# Barebones_ATMega328P.net
KiCad netlist of a schematic drawn in EAGLE
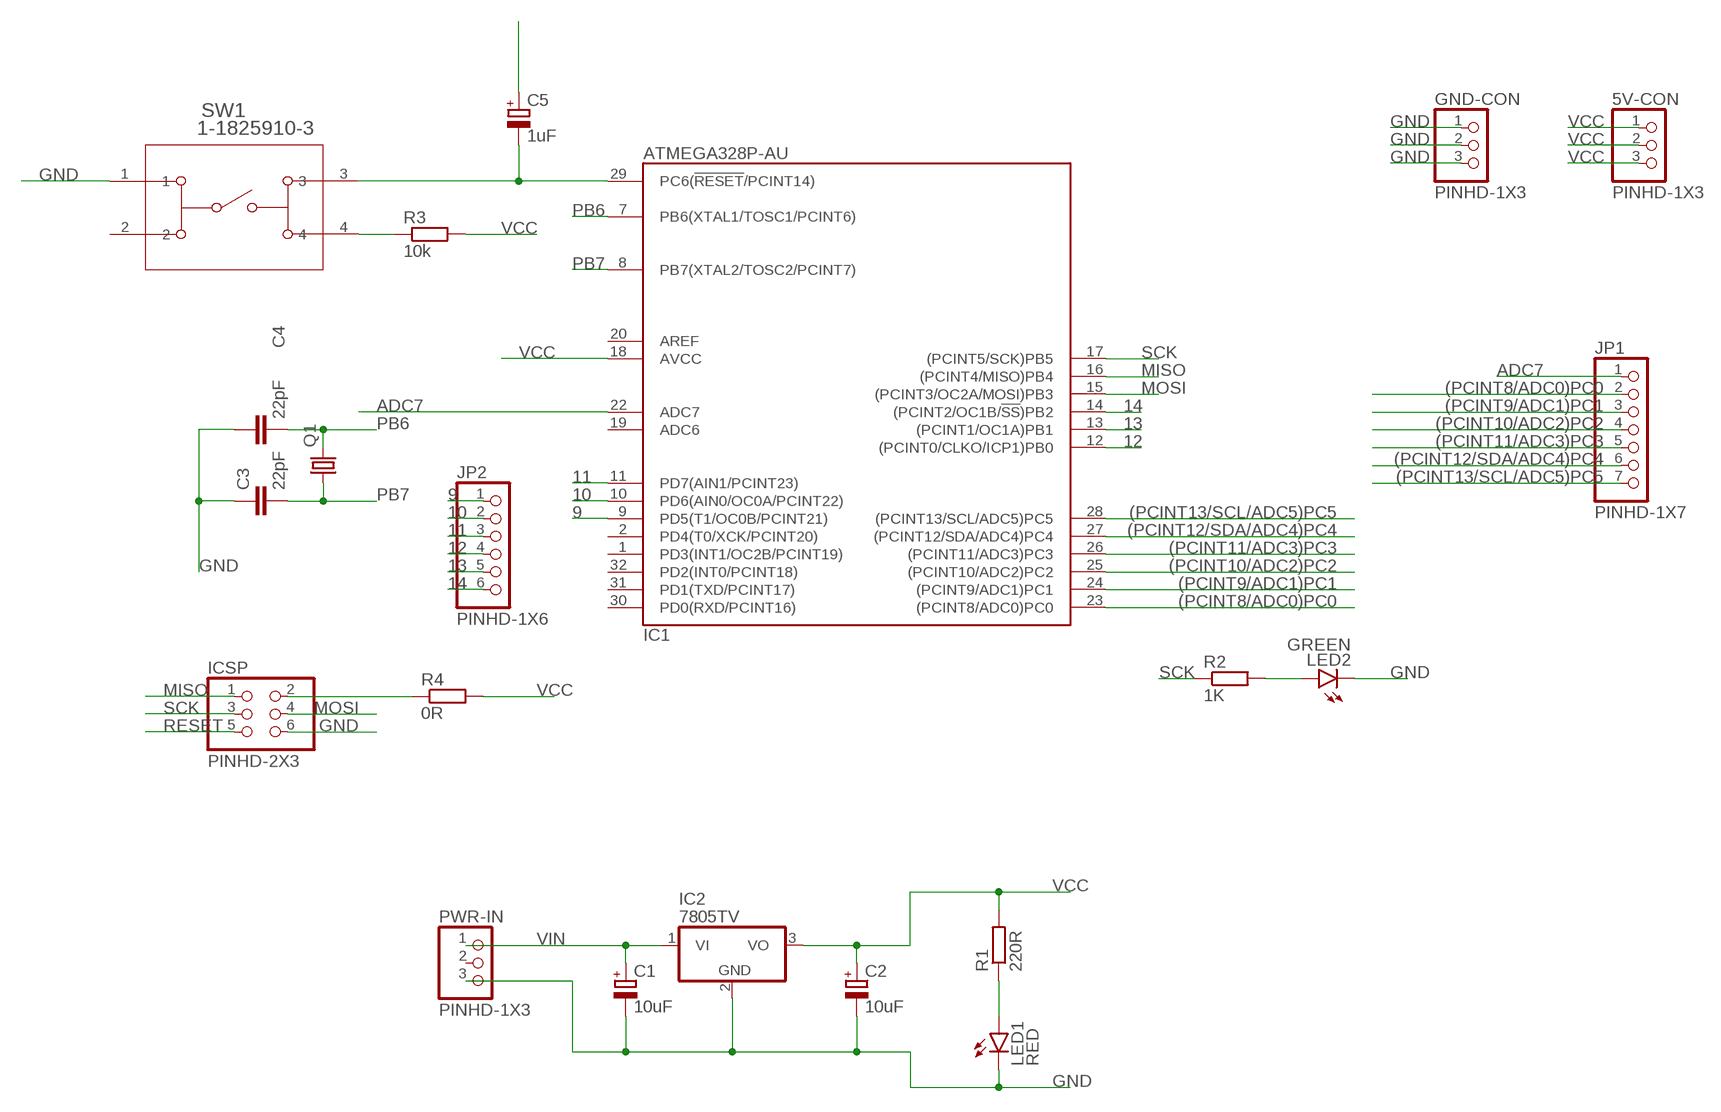
[diagram p0: schematic, sheet 1]

(export (version "E")
  (design (tool "Eeschema 10.0.6"))
  (components
    (comp (ref "5V-CON")
      (value "PINHD-1X3")
      (footprint "eagle-import:1X03")
      (libsource (lib "eagle-import") (part "PINHD-1X3"))
    )
    (comp (ref "C1")
      (value "10uF")
      (footprint "eagle-import:E5-8,5")
      (libsource (lib "eagle-import") (part "CPOL-EUE5-8.5"))
    )
    (comp (ref "C2")
      (value "10uF")
      (footprint "eagle-import:E5-8,5")
      (libsource (lib "eagle-import") (part "CPOL-EUE5-8.5"))
    )
    (comp (ref "C3")
      (value "22pF")
      (footprint "eagle-import:C025-025X050")
      (libsource (lib "eagle-import") (part "C-EU025-025X050"))
    )
    (comp (ref "C4")
      (value "22pF")
      (footprint "eagle-import:C025-025X050")
      (libsource (lib "eagle-import") (part "C-EU025-025X050"))
    )
    (comp (ref "C5")
      (value "1uF")
      (footprint "eagle-import:E5-8,5")
      (libsource (lib "eagle-import") (part "CPOL-EUE5-8.5"))
    )
    (comp (ref "GND-CON")
      (value "PINHD-1X3")
      (footprint "eagle-import:1X03")
      (libsource (lib "eagle-import") (part "PINHD-1X3"))
    )
    (comp (ref "IC1")
      (value "ATMEGA328P-AU")
      (footprint "eagle-import:QFP32_7X7_0.80")
      (libsource (lib "eagle-import") (part "ATMEGA8P-AU32"))
    )
    (comp (ref "IC2")
      (value "7805TV")
      (footprint "eagle-import:TO220V")
      (libsource (lib "eagle-import") (part "78TV05"))
    )
    (comp (ref "ICSP")
      (value "PINHD-2X3")
      (footprint "eagle-import:2X03")
      (libsource (lib "eagle-import") (part "PINHD-2X3"))
    )
    (comp (ref "JP1")
      (value "PINHD-1X7")
      (footprint "eagle-import:1X07")
      (libsource (lib "eagle-import") (part "PINHD-1X7"))
    )
    (comp (ref "JP2")
      (value "PINHD-1X6")
      (footprint "eagle-import:1X06")
      (libsource (lib "eagle-import") (part "PINHD-1X6"))
    )
    (comp (ref "LED1")
      (value "RED")
      (footprint "eagle-import:LED3MM")
      (libsource (lib "eagle-import") (part "LED3MM"))
    )
    (comp (ref "LED2")
      (value "GREEN")
      (footprint "eagle-import:LED3MM")
      (libsource (lib "eagle-import") (part "LED3MM"))
    )
    (comp (ref "PWR-IN")
      (value "PINHD-1X3")
      (footprint "eagle-import:1X03")
      (libsource (lib "eagle-import") (part "PINHD-1X3"))
    )
    (comp (ref "Q1")
      (value "CRYSTALHC49S")
      (footprint "eagle-import:HC49_S")
      (libsource (lib "eagle-import") (part "CRYSTALHC49S"))
    )
    (comp (ref "R1")
      (value "220R")
      (footprint "eagle-import:0207_10")
      (libsource (lib "eagle-import") (part "R-EU_0207/10"))
    )
    (comp (ref "R2")
      (value "1K")
      (footprint "eagle-import:0207_10")
      (libsource (lib "eagle-import") (part "R-EU_0207/10"))
    )
    (comp (ref "R3")
      (value "10k")
      (footprint "eagle-import:0207_10")
      (libsource (lib "eagle-import") (part "R-EU_0207/10"))
    )
    (comp (ref "R4")
      (value "0R")
      (footprint "eagle-import:0207_10")
      (libsource (lib "eagle-import") (part "R-EU_0207/10"))
    )
    (comp (ref "SW1")
      (value "1-1825910-3")
      (footprint "eagle-import:SW4_1825910-D")
      (fields (field (name "COPYRIGHT") "Copyright (C) 2016 Accelerated Designs. All rights reserved"))
      (libsource (lib "eagle-import") (part "1-1825910-3"))
    )
  )
  (nets
    (net (code "1") (name "/(PCINT8{slash}ADC0)PC0") (class "Default")
      (node (ref "IC1") (pin "23") (pinfunction "(PCINT8/ADC0)PC0_23") (pintype "bidirectional"))
      (node (ref "JP1") (pin "2") (pinfunction "2_2") (pintype "passive"))
    )
    (net (code "2") (name "/(PCINT9{slash}ADC1)PC1") (class "Default")
      (node (ref "IC1") (pin "24") (pinfunction "(PCINT9/ADC1)PC1_24") (pintype "bidirectional"))
      (node (ref "JP1") (pin "3") (pinfunction "3_3") (pintype "passive"))
    )
    (net (code "3") (name "/(PCINT10{slash}ADC2)PC2") (class "Default")
      (node (ref "IC1") (pin "25") (pinfunction "(PCINT10/ADC2)PC2_25") (pintype "bidirectional"))
      (node (ref "JP1") (pin "4") (pinfunction "4_4") (pintype "passive"))
    )
    (net (code "4") (name "/(PCINT11{slash}ADC3)PC3") (class "Default")
      (node (ref "IC1") (pin "26") (pinfunction "(PCINT11/ADC3)PC3_26") (pintype "bidirectional"))
      (node (ref "JP1") (pin "5") (pinfunction "5_5") (pintype "passive"))
    )
    (net (code "5") (name "/(PCINT12{slash}SDA{slash}ADC4)PC4") (class "Default")
      (node (ref "IC1") (pin "27") (pinfunction "(PCINT12/SDA/ADC4)PC4_27") (pintype "bidirectional"))
      (node (ref "JP1") (pin "6") (pinfunction "6_6") (pintype "passive"))
    )
    (net (code "6") (name "/(PCINT13{slash}SCL{slash}ADC5)PC5") (class "Default")
      (node (ref "IC1") (pin "28") (pinfunction "(PCINT13/SCL/ADC5)PC5_28") (pintype "bidirectional"))
      (node (ref "JP1") (pin "7") (pinfunction "7_7") (pintype "passive"))
    )
    (net (code "7") (name "/9") (class "Default")
      (node (ref "IC1") (pin "9") (pinfunction "PD5(T1/OC0B/PCINT21)_9") (pintype "bidirectional"))
      (node (ref "JP2") (pin "1") (pinfunction "1_1") (pintype "passive"))
    )
    (net (code "8") (name "/10") (class "Default")
      (node (ref "IC1") (pin "10") (pinfunction "PD6(AIN0/OC0A/PCINT22)_10") (pintype "bidirectional"))
      (node (ref "JP2") (pin "2") (pinfunction "2_2") (pintype "passive"))
    )
    (net (code "9") (name "/11") (class "Default")
      (node (ref "IC1") (pin "11") (pinfunction "PD7(AIN1/PCINT23)_11") (pintype "bidirectional"))
      (node (ref "JP2") (pin "3") (pinfunction "3_3") (pintype "passive"))
    )
    (net (code "10") (name "/12") (class "Default")
      (node (ref "IC1") (pin "12") (pinfunction "(PCINT0/CLKO/ICP1)PB0_12") (pintype "bidirectional"))
      (node (ref "JP2") (pin "4") (pinfunction "4_4") (pintype "passive"))
    )
    (net (code "11") (name "/13") (class "Default")
      (node (ref "IC1") (pin "13") (pinfunction "(PCINT1/OC1A)PB1_13") (pintype "bidirectional"))
      (node (ref "JP2") (pin "5") (pinfunction "5_5") (pintype "passive"))
    )
    (net (code "12") (name "/14") (class "Default")
      (node (ref "IC1") (pin "14") (pinfunction "(PCINT2/OC1B/~{SS})PB2_14") (pintype "bidirectional"))
      (node (ref "JP2") (pin "6") (pinfunction "6_6") (pintype "passive"))
    )
    (net (code "13") (name "/ADC7") (class "Default")
      (node (ref "IC1") (pin "22") (pinfunction "ADC7_22") (pintype "bidirectional"))
      (node (ref "JP1") (pin "1") (pinfunction "1_1") (pintype "passive"))
    )
    (net (code "14") (name "/GND") (class "Default")
      (node (ref "C1") (pin "-") (pinfunction "-_-") (pintype "passive"))
      (node (ref "C2") (pin "-") (pinfunction "-_-") (pintype "passive"))
      (node (ref "C3") (pin "1") (pinfunction "1_1") (pintype "passive"))
      (node (ref "C4") (pin "1") (pinfunction "1_1") (pintype "passive"))
      (node (ref "GND-CON") (pin "1") (pinfunction "1_1") (pintype "passive"))
      (node (ref "GND-CON") (pin "2") (pinfunction "2_2") (pintype "passive"))
      (node (ref "GND-CON") (pin "3") (pinfunction "3_3") (pintype "passive"))
      (node (ref "IC2") (pin "2") (pinfunction "GND_2") (pintype "passive"))
      (node (ref "ICSP") (pin "6") (pinfunction "6_6") (pintype "passive"))
      (node (ref "LED1") (pin "K") (pinfunction "C_K") (pintype "passive"))
      (node (ref "LED2") (pin "K") (pinfunction "C_K") (pintype "passive"))
      (node (ref "PWR-IN") (pin "3") (pinfunction "3_3") (pintype "passive"))
      (node (ref "SW1") (pin "1") (pinfunction "1_1") (pintype "passive"))
    )
    (net (code "15") (name "/MISO") (class "Default")
      (node (ref "IC1") (pin "16") (pinfunction "(PCINT4/MISO)PB4_16") (pintype "bidirectional"))
      (node (ref "ICSP") (pin "1") (pinfunction "1_1") (pintype "passive"))
    )
    (net (code "16") (name "/MOSI") (class "Default")
      (node (ref "IC1") (pin "15") (pinfunction "(PCINT3/OC2A/MOSI)PB3_15") (pintype "bidirectional"))
      (node (ref "ICSP") (pin "4") (pinfunction "4_4") (pintype "passive"))
    )
    (net (code "17") (name "/PB6") (class "Default")
      (node (ref "C4") (pin "2") (pinfunction "2_2") (pintype "passive"))
      (node (ref "IC1") (pin "7") (pinfunction "PB6(XTAL1/TOSC1/PCINT6)_7") (pintype "bidirectional"))
      (node (ref "Q1") (pin "2") (pinfunction "2_2") (pintype "passive"))
    )
    (net (code "18") (name "/PB7") (class "Default")
      (node (ref "C3") (pin "2") (pinfunction "2_2") (pintype "passive"))
      (node (ref "IC1") (pin "8") (pinfunction "PB7(XTAL2/TOSC2/PCINT7)_8") (pintype "bidirectional"))
      (node (ref "Q1") (pin "1") (pinfunction "1_1") (pintype "passive"))
    )
    (net (code "19") (name "/RESET") (class "Default")
      (node (ref "C5") (pin "+") (pinfunction "+_+") (pintype "passive"))
      (node (ref "ICSP") (pin "5") (pinfunction "5_5") (pintype "passive"))
    )
    (net (code "20") (name "/SCK") (class "Default")
      (node (ref "IC1") (pin "17") (pinfunction "(PCINT5/SCK)PB5_17") (pintype "bidirectional"))
      (node (ref "ICSP") (pin "3") (pinfunction "3_3") (pintype "passive"))
      (node (ref "R2") (pin "1") (pinfunction "1_1") (pintype "passive"))
    )
    (net (code "21") (name "/VCC") (class "Default")
      (node (ref "5V-CON") (pin "1") (pinfunction "1_1") (pintype "passive"))
      (node (ref "5V-CON") (pin "2") (pinfunction "2_2") (pintype "passive"))
      (node (ref "5V-CON") (pin "3") (pinfunction "3_3") (pintype "passive"))
      (node (ref "C2") (pin "+") (pinfunction "+_+") (pintype "passive"))
      (node (ref "IC1") (pin "18") (pinfunction "AVCC_18") (pintype "power_in"))
      (node (ref "IC2") (pin "3") (pinfunction "VO_3") (pintype "passive"))
      (node (ref "R1") (pin "2") (pinfunction "2_2") (pintype "passive"))
      (node (ref "R3") (pin "2") (pinfunction "2_2") (pintype "passive"))
      (node (ref "R4") (pin "2") (pinfunction "2_2") (pintype "passive"))
    )
    (net (code "22") (name "/VIN") (class "Default")
      (node (ref "C1") (pin "+") (pinfunction "+_+") (pintype "passive"))
      (node (ref "IC2") (pin "1") (pinfunction "VI_1") (pintype "input"))
      (node (ref "PWR-IN") (pin "1") (pinfunction "1_1") (pintype "passive"))
    )
    (net (code "23") (name "Net-(IC1A-PC6(~{RESET}{slash}PCINT14))") (class "Default")
      (node (ref "C5") (pin "-") (pinfunction "-_-") (pintype "passive"))
      (node (ref "IC1") (pin "29") (pinfunction "PC6(~{RESET}/PCINT14)_29") (pintype "bidirectional"))
      (node (ref "SW1") (pin "3") (pinfunction "3_3") (pintype "passive"))
    )
    (net (code "24") (name "Net-(ICSP-Pad2)") (class "Default")
      (node (ref "ICSP") (pin "2") (pinfunction "2_2") (pintype "passive"))
      (node (ref "R4") (pin "1") (pinfunction "1_1") (pintype "passive"))
    )
    (net (code "25") (name "Net-(LED1-PadA)") (class "Default")
      (node (ref "LED1") (pin "A") (pinfunction "A_A") (pintype "passive"))
      (node (ref "R1") (pin "1") (pinfunction "1_1") (pintype "passive"))
    )
    (net (code "26") (name "Net-(LED2-PadA)") (class "Default")
      (node (ref "LED2") (pin "A") (pinfunction "A_A") (pintype "passive"))
      (node (ref "R2") (pin "2") (pinfunction "2_2") (pintype "passive"))
    )
    (net (code "27") (name "Net-(R3-Pad1)") (class "Default")
      (node (ref "R3") (pin "1") (pinfunction "1_1") (pintype "passive"))
      (node (ref "SW1") (pin "4") (pinfunction "4_4") (pintype "passive"))
    )
    (net (code "28") (name "unconnected-(IC1A-ADC6-Pad19)") (class "Default")
      (node (ref "IC1") (pin "19") (pinfunction "ADC6_19") (pintype "bidirectional"))
    )
    (net (code "29") (name "unconnected-(IC1A-AREF-Pad20)") (class "Default")
      (node (ref "IC1") (pin "20") (pinfunction "AREF_20") (pintype "passive"))
    )
    (net (code "30") (name "unconnected-(IC1A-PD0(RXD{slash}PCINT16)-Pad30)") (class "Default")
      (node (ref "IC1") (pin "30") (pinfunction "PD0(RXD/PCINT16)_30") (pintype "bidirectional"))
    )
    (net (code "31") (name "unconnected-(IC1A-PD1(TXD{slash}PCINT17)-Pad31)") (class "Default")
      (node (ref "IC1") (pin "31") (pinfunction "PD1(TXD/PCINT17)_31") (pintype "bidirectional"))
    )
    (net (code "32") (name "unconnected-(IC1A-PD2(INT0{slash}PCINT18)-Pad32)") (class "Default")
      (node (ref "IC1") (pin "32") (pinfunction "PD2(INT0/PCINT18)_32") (pintype "bidirectional"))
    )
    (net (code "33") (name "unconnected-(IC1A-PD3(INT1{slash}OC2B{slash}PCINT19)-Pad1)") (class "Default")
      (node (ref "IC1") (pin "1") (pinfunction "PD3(INT1/OC2B/PCINT19)_1") (pintype "bidirectional"))
    )
    (net (code "34") (name "unconnected-(IC1A-PD4(T0{slash}XCK{slash}PCINT20)-Pad2)") (class "Default")
      (node (ref "IC1") (pin "2") (pinfunction "PD4(T0/XCK/PCINT20)_2") (pintype "bidirectional"))
    )
    (net (code "35") (name "unconnected-(PWR-IN-Pad2)") (class "Default")
      (node (ref "PWR-IN") (pin "2") (pinfunction "2_2") (pintype "passive"))
    )
    (net (code "36") (name "unconnected-(SW1-Pad2)") (class "Default")
      (node (ref "SW1") (pin "2") (pinfunction "2_2") (pintype "passive"))
    )
  )
)
